# SOIL_MOISTURE_3IN.net
KiCad netlist of a schematic drawn in Altium Designer
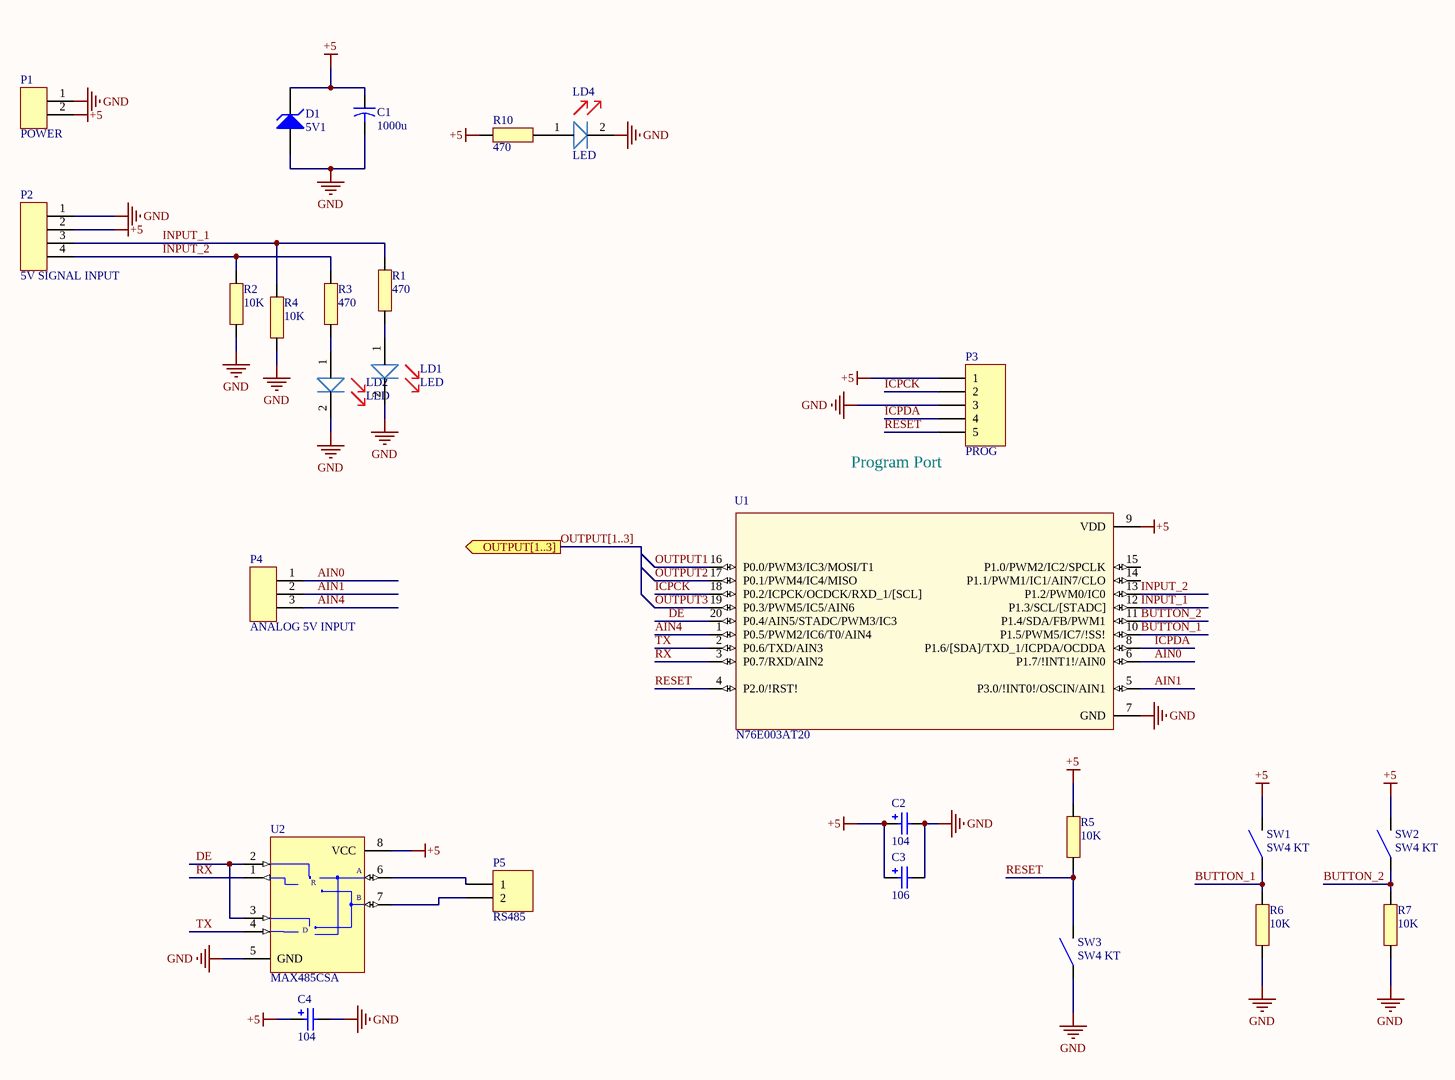
[diagram p0: SOIL_MOISTURE_3IN.SchDoc]

(export (version "E")
  (design (tool "Eeschema 10.0.6"))
  (components
    (comp (ref "C1")
      (value "1000u")
      (footprint "CAPR5-4X5")
      (description "Capacitor")
      (fields (field (name "PUBLISHER") "Altium Limited"))
      (libsource (lib "Miscellaneous Devices") (part "Cap2"))
    )
    (comp (ref "C2")
      (value "104")
      (footprint "Resistor")
      (description "Polarized Capacitor (Surface Mount)")
      (fields (field (name "PUBLISHER") "Altium Limited"))
      (libsource (lib "Miscellaneous Devices") (part "Cap Pol3"))
    )
    (comp (ref "C3")
      (value "106")
      (footprint "Resistor")
      (description "Polarized Capacitor (Surface Mount)")
      (fields (field (name "PUBLISHER") "Altium Limited"))
      (libsource (lib "Miscellaneous Devices") (part "Cap Pol3"))
    )
    (comp (ref "C4")
      (value "104")
      (footprint "Resistor")
      (description "Polarized Capacitor (Surface Mount)")
      (fields (field (name "PUBLISHER") "Altium Limited"))
      (libsource (lib "Miscellaneous Devices") (part "Cap Pol3"))
    )
    (comp (ref "D1")
      (value "5V1")
      (footprint "DO-41")
      (description "Zener Diode")
      (fields (field (name "PUBLISHER") "Altium Limited"))
      (libsource (lib "Miscellaneous Devices") (part "D Zener"))
    )
    (comp (ref "LD1")
      (value "LED")
      (footprint "LED_SMD")
      (description "0805")
      (fields (field (name "PUBLISHER") "Altium Limited"))
      (libsource (lib "TOAN_ONG_Library") (part "LED_SMD"))
    )
    (comp (ref "LD2")
      (value "LED")
      (footprint "LED_SMD")
      (description "0805")
      (fields (field (name "PUBLISHER") "Altium Limited"))
      (libsource (lib "TOAN_ONG_Library") (part "LED_SMD"))
    )
    (comp (ref "LD4")
      (value "LED")
      (footprint "LED_SMD")
      (description "0805")
      (fields (field (name "PUBLISHER") "Altium Limited"))
      (libsource (lib "TOAN_ONG_Library") (part "LED_SMD"))
    )
    (comp (ref "P1")
      (value "POWER")
      (footprint "2 PIN TERMINAL")
      (description "Header, 2-Pin")
      (fields (field (name "PUBLISHER") "Altium Limited"))
      (libsource (lib "TOAN_ONG_Library") (part "2 PIN TERMINAL"))
    )
    (comp (ref "P2")
      (value "5V SIGNAL INPUT")
      (footprint "4 PIN TERMINAL")
      (description "Header, 4-Pin")
      (fields (field (name "PUBLISHER") "Altium Limited"))
      (libsource (lib "TOAN_ONG_Library") (part "4 PIN TERMINAL"))
    )
    (comp (ref "P3")
      (value "PROG")
      (footprint "HDR1X5")
      (description "Header, 5-Pin")
      (fields (field (name "PUBLISHER") "Altium Limited"))
      (libsource (lib "Miscellaneous Connectors") (part "Header 5"))
    )
    (comp (ref "P4")
      (value "ANALOG 5V INPUT")
      (footprint "3 PIN TERMINAL")
      (description "Header, 2-Pin")
      (fields (field (name "PUBLISHER") "Altium Limited"))
      (libsource (lib "TOAN_ONG_Library") (part "3 PIN TERMINAL"))
    )
    (comp (ref "P5")
      (value "RS485")
      (footprint "HDR1X2")
      (description "Header, 2-Pin")
      (fields (field (name "PUBLISHER") "Altium Limited"))
      (libsource (lib "Miscellaneous Connectors") (part "Header 2"))
    )
    (comp (ref "R1")
      (value "470")
      (footprint "Resistor")
      (description "Resistor")
      (fields (field (name "PUBLISHER") "Altium Limited"))
      (libsource (lib "TOAN_ONG_Library") (part "Resistor"))
    )
    (comp (ref "R2")
      (value "10K")
      (footprint "Resistor")
      (description "Resistor")
      (fields (field (name "PUBLISHER") "Altium Limited"))
      (libsource (lib "TOAN_ONG_Library") (part "Resistor"))
    )
    (comp (ref "R3")
      (value "470")
      (footprint "Resistor")
      (description "Resistor")
      (fields (field (name "PUBLISHER") "Altium Limited"))
      (libsource (lib "TOAN_ONG_Library") (part "Resistor"))
    )
    (comp (ref "R4")
      (value "10K")
      (footprint "Resistor")
      (description "Resistor")
      (fields (field (name "PUBLISHER") "Altium Limited"))
      (libsource (lib "TOAN_ONG_Library") (part "Resistor"))
    )
    (comp (ref "R5")
      (value "10K")
      (footprint "Resistor")
      (description "Resistor")
      (fields (field (name "PUBLISHER") "Altium Limited"))
      (libsource (lib "") (part "Resistor_1"))
    )
    (comp (ref "R6")
      (value "10K")
      (footprint "Resistor")
      (description "Resistor")
      (fields (field (name "PUBLISHER") "Altium Limited"))
      (libsource (lib "") (part "Resistor_1"))
    )
    (comp (ref "R7")
      (value "10K")
      (footprint "Resistor")
      (description "Resistor")
      (fields (field (name "PUBLISHER") "Altium Limited"))
      (libsource (lib "") (part "Resistor_1"))
    )
    (comp (ref "R10")
      (value "470")
      (footprint "Resistor")
      (description "Resistor")
      (fields (field (name "PUBLISHER") "Altium Limited"))
      (libsource (lib "") (part "Resistor_2"))
    )
    (comp (ref "SW1")
      (value "SW4 KT")
      (footprint "SW4_6x6x8mm")
      (libsource (lib "TOAN_ONG_Library") (part "SW4 KT"))
    )
    (comp (ref "SW2")
      (value "SW4 KT")
      (footprint "SW4_6x6x8mm")
      (libsource (lib "TOAN_ONG_Library") (part "SW4 KT"))
    )
    (comp (ref "SW3")
      (value "SW4 KT")
      (footprint "SW4_6x6x8mm")
      (libsource (lib "TOAN_ONG_Library") (part "SW4 KT"))
    )
    (comp (ref "U1")
      (value "N76E003AT20")
      (footprint "*SOP65P640X120-20N")
      (description "8051 Mcu, Shape: t")
      (fields (field (name "MP") "N76E003AT20-T") (field (name "MF") "Nuvoton"))
      (libsource (lib "N76E003AT20") (part "N76E003AT20"))
    )
    (comp (ref "U2")
      (value "MAX485CSA")
      (footprint "NSO8_N")
      (description "Low-Power, Slew-Rate-Limited RS-485/RS-422 Transceiver")
      (fields (field (name "PUBLISHER") "Altium Limited"))
      (libsource (lib "Maxim Communication Transceiver") (part "MAX485CSA"))
    )
  )
  (nets
    (net (code "1") (name "+5") (class "Default")
      (node (ref "C1") (pin "1") (pinfunction "1_1") (pintype "passive"))
      (node (ref "C2") (pin "1") (pinfunction "1_1") (pintype "passive"))
      (node (ref "C3") (pin "1") (pinfunction "1_1") (pintype "passive"))
      (node (ref "C4") (pin "1") (pinfunction "1_1") (pintype "passive"))
      (node (ref "D1") (pin "2") (pinfunction "K_2") (pintype "passive"))
      (node (ref "P1") (pin "2") (pinfunction "2_2") (pintype "passive"))
      (node (ref "P2") (pin "2") (pinfunction "2_2") (pintype "passive"))
      (node (ref "P3") (pin "1") (pinfunction "1_1") (pintype "passive"))
      (node (ref "R10") (pin "1") (pinfunction "1_1") (pintype "passive"))
      (node (ref "R5") (pin "2") (pinfunction "2_2") (pintype "passive"))
      (node (ref "SW1") (pin "2") (pinfunction "2_2") (pintype "passive"))
      (node (ref "SW2") (pin "2") (pinfunction "2_2") (pintype "passive"))
      (node (ref "U1") (pin "9") (pinfunction "VDD_9") (pintype "power_in"))
      (node (ref "U2") (pin "8") (pinfunction "VCC_8") (pintype "power_in"))
    )
    (net (code "2") (name "/AIN0") (class "Default")
      (node (ref "P4") (pin "1") (pinfunction "1_1") (pintype "passive"))
      (node (ref "U1") (pin "6") (pinfunction "P1.7/!INT1!/AIN0_6") (pintype "bidirectional"))
    )
    (net (code "3") (name "/AIN1") (class "Default")
      (node (ref "P4") (pin "2") (pinfunction "2_2") (pintype "passive"))
      (node (ref "U1") (pin "5") (pinfunction "P3.0/!INT0!/OSCIN/AIN1_5") (pintype "bidirectional"))
    )
    (net (code "4") (name "/AIN4") (class "Default")
      (node (ref "P4") (pin "3") (pinfunction "3_3") (pintype "passive"))
      (node (ref "U1") (pin "1") (pinfunction "P0.5/PWM2/IC6/T0/AIN4_1") (pintype "bidirectional"))
    )
    (net (code "5") (name "/BUTTON_1") (class "Default")
      (node (ref "R6") (pin "2") (pinfunction "2_2") (pintype "passive"))
      (node (ref "SW1") (pin "1") (pinfunction "1_1") (pintype "passive"))
      (node (ref "U1") (pin "10") (pinfunction "P1.5/PWM5/IC7/!SS!_10") (pintype "bidirectional"))
    )
    (net (code "6") (name "/BUTTON_2") (class "Default")
      (node (ref "R7") (pin "2") (pinfunction "2_2") (pintype "passive"))
      (node (ref "SW2") (pin "1") (pinfunction "1_1") (pintype "passive"))
      (node (ref "U1") (pin "11") (pinfunction "P1.4/SDA/FB/PWM1_11") (pintype "bidirectional"))
    )
    (net (code "7") (name "/DE") (class "Default")
      (node (ref "U1") (pin "20") (pinfunction "P0.4/AIN5/STADC/PWM3/IC3_20") (pintype "bidirectional"))
      (node (ref "U2") (pin "2") (pinfunction "~{RE}_2") (pintype "input"))
      (node (ref "U2") (pin "3") (pinfunction "DE_3") (pintype "input"))
    )
    (net (code "8") (name "/ICPCK") (class "Default")
      (node (ref "P3") (pin "2") (pinfunction "2_2") (pintype "passive"))
      (node (ref "U1") (pin "18") (pinfunction "P0.2/ICPCK/OCDCK/RXD_1/[SCL]_18") (pintype "bidirectional"))
    )
    (net (code "9") (name "/ICPDA") (class "Default")
      (node (ref "P3") (pin "4") (pinfunction "4_4") (pintype "passive"))
      (node (ref "U1") (pin "8") (pinfunction "P1.6/[SDA]/TXD_1/ICPDA/OCDDA_8") (pintype "bidirectional"))
    )
    (net (code "10") (name "/INPUT_1") (class "Default")
      (node (ref "P2") (pin "3") (pinfunction "3_3") (pintype "passive"))
      (node (ref "R1") (pin "1") (pinfunction "1_1") (pintype "passive"))
      (node (ref "R4") (pin "1") (pinfunction "1_1") (pintype "passive"))
      (node (ref "U1") (pin "12") (pinfunction "P1.3/SCL/[STADC]_12") (pintype "bidirectional"))
    )
    (net (code "11") (name "/INPUT_2") (class "Default")
      (node (ref "P2") (pin "4") (pinfunction "4_4") (pintype "passive"))
      (node (ref "R2") (pin "1") (pinfunction "1_1") (pintype "passive"))
      (node (ref "R3") (pin "1") (pinfunction "1_1") (pintype "passive"))
      (node (ref "U1") (pin "13") (pinfunction "P1.2/PWM0/IC0_13") (pintype "bidirectional"))
    )
    (net (code "12") (name "/OUTPUT1") (class "Default")
      (node (ref "U1") (pin "16") (pinfunction "P0.0/PWM3/IC3/MOSI/T1_16") (pintype "bidirectional"))
    )
    (net (code "13") (name "/OUTPUT2") (class "Default")
      (node (ref "U1") (pin "17") (pinfunction "P0.1/PWM4/IC4/MISO_17") (pintype "bidirectional"))
    )
    (net (code "14") (name "/OUTPUT3") (class "Default")
      (node (ref "U1") (pin "19") (pinfunction "P0.3/PWM5/IC5/AIN6_19") (pintype "bidirectional"))
    )
    (net (code "16") (name "/RESET") (class "Default")
      (node (ref "P3") (pin "5") (pinfunction "5_5") (pintype "passive"))
      (node (ref "R5") (pin "1") (pinfunction "1_1") (pintype "passive"))
      (node (ref "SW3") (pin "2") (pinfunction "2_2") (pintype "passive"))
      (node (ref "U1") (pin "4") (pinfunction "P2.0/!RST!_4") (pintype "bidirectional"))
    )
    (net (code "17") (name "/RX") (class "Default")
      (node (ref "U1") (pin "3") (pinfunction "P0.7/RXD/AIN2_3") (pintype "bidirectional"))
      (node (ref "U2") (pin "1") (pinfunction "RO_1") (pintype "output"))
    )
    (net (code "18") (name "/TX") (class "Default")
      (node (ref "U1") (pin "2") (pinfunction "P0.6/TXD/AIN3_2") (pintype "bidirectional"))
      (node (ref "U2") (pin "4") (pinfunction "DI_4") (pintype "input"))
    )
    (net (code "19") (name "GND") (class "Default")
      (node (ref "C1") (pin "2") (pinfunction "2_2") (pintype "passive"))
      (node (ref "C2") (pin "2") (pinfunction "2_2") (pintype "passive"))
      (node (ref "C3") (pin "2") (pinfunction "2_2") (pintype "passive"))
      (node (ref "C4") (pin "2") (pinfunction "2_2") (pintype "passive"))
      (node (ref "D1") (pin "1") (pinfunction "A_1") (pintype "passive"))
      (node (ref "LD1") (pin "2") (pinfunction "2_2") (pintype "passive"))
      (node (ref "LD2") (pin "2") (pinfunction "2_2") (pintype "passive"))
      (node (ref "LD4") (pin "2") (pinfunction "2_2") (pintype "passive"))
      (node (ref "P1") (pin "1") (pinfunction "1_1") (pintype "passive"))
      (node (ref "P2") (pin "1") (pinfunction "1_1") (pintype "passive"))
      (node (ref "P3") (pin "3") (pinfunction "3_3") (pintype "passive"))
      (node (ref "R2") (pin "2") (pinfunction "2_2") (pintype "passive"))
      (node (ref "R4") (pin "2") (pinfunction "2_2") (pintype "passive"))
      (node (ref "R6") (pin "1") (pinfunction "1_1") (pintype "passive"))
      (node (ref "R7") (pin "1") (pinfunction "1_1") (pintype "passive"))
      (node (ref "SW3") (pin "1") (pinfunction "1_1") (pintype "passive"))
      (node (ref "U1") (pin "7") (pinfunction "GND_7") (pintype "power_in"))
      (node (ref "U2") (pin "5") (pinfunction "GND_5") (pintype "power_in"))
    )
    (net (code "20") (name "Net-(LD1-Pad1)") (class "Default")
      (node (ref "LD1") (pin "1") (pinfunction "1_1") (pintype "passive"))
      (node (ref "R1") (pin "2") (pinfunction "2_2") (pintype "passive"))
    )
    (net (code "21") (name "Net-(LD2-Pad1)") (class "Default")
      (node (ref "LD2") (pin "1") (pinfunction "1_1") (pintype "passive"))
      (node (ref "R3") (pin "2") (pinfunction "2_2") (pintype "passive"))
    )
    (net (code "22") (name "Net-(LD4-Pad1)") (class "Default")
      (node (ref "LD4") (pin "1") (pinfunction "1_1") (pintype "passive"))
      (node (ref "R10") (pin "2") (pinfunction "2_2") (pintype "passive"))
    )
    (net (code "23") (name "Net-(U2-A)") (class "Default")
      (node (ref "P5") (pin "1") (pinfunction "1_1") (pintype "passive"))
      (node (ref "U2") (pin "6") (pinfunction "A_6") (pintype "bidirectional"))
    )
    (net (code "24") (name "Net-(U2-B)") (class "Default")
      (node (ref "P5") (pin "2") (pinfunction "2_2") (pintype "passive"))
      (node (ref "U2") (pin "7") (pinfunction "B_7") (pintype "bidirectional"))
    )
    (net (code "25") (name "unconnected-(U1-P1.0{slash}PWM2{slash}IC2{slash}SPCLK-Pad15)") (class "Default")
      (node (ref "U1") (pin "15") (pinfunction "P1.0/PWM2/IC2/SPCLK_15") (pintype "bidirectional"))
    )
    (net (code "26") (name "unconnected-(U1-P1.1{slash}PWM1{slash}IC1{slash}AIN7{slash}CLO-Pad14)") (class "Default")
      (node (ref "U1") (pin "14") (pinfunction "P1.1/PWM1/IC1/AIN7/CLO_14") (pintype "bidirectional"))
    )
  )
)
